# LMH6881-Breakout.net
KiCad netlist of a schematic drawn in EAGLE
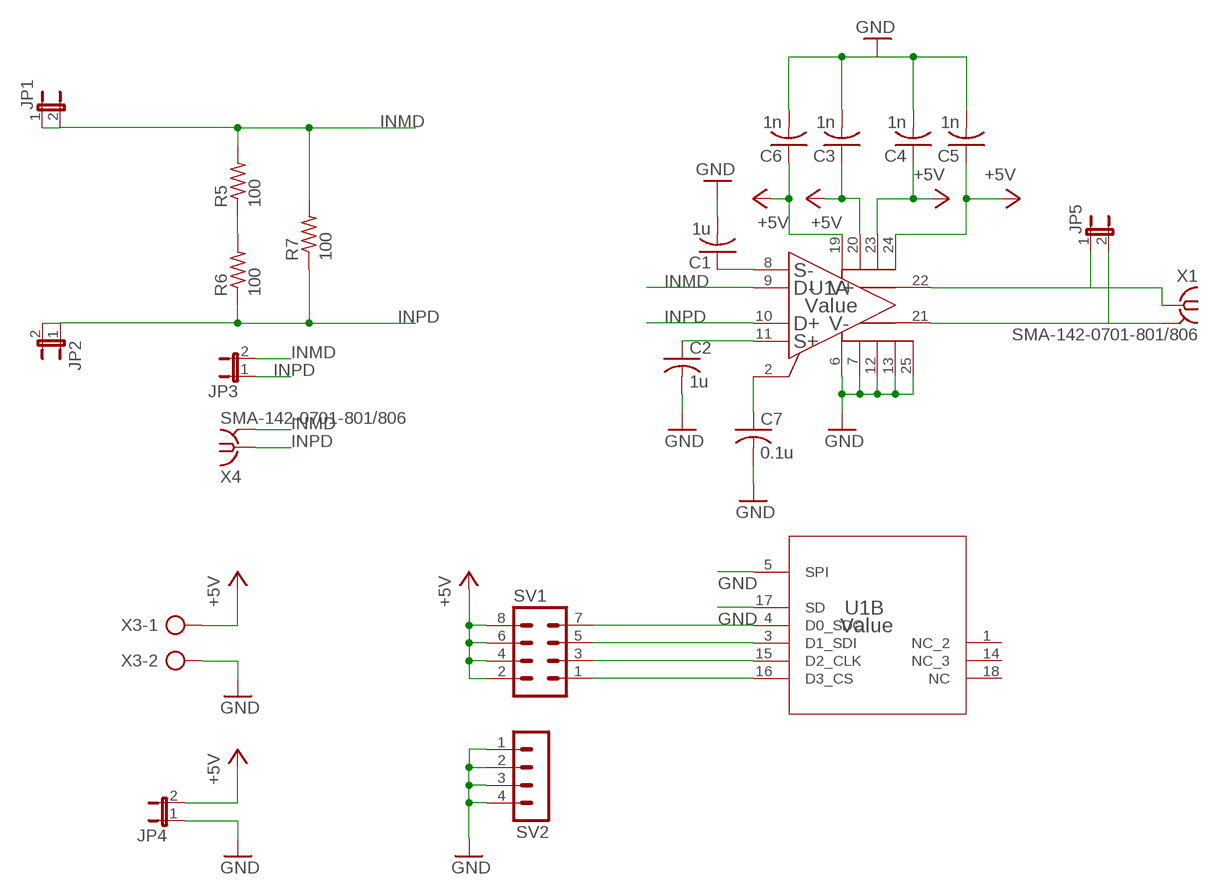
[diagram p0: schematic, sheet 1]

(export (version "E")
  (design (tool "Eeschema 10.0.6"))
  (components
    (comp (ref "C1")
      (value "1u")
      (footprint "eagle-import:C0805")
      (libsource (lib "eagle-import") (part "C-USC0805"))
    )
    (comp (ref "C2")
      (value "1u")
      (footprint "eagle-import:C0805")
      (libsource (lib "eagle-import") (part "C-USC0805"))
    )
    (comp (ref "C3")
      (value "1n")
      (footprint "eagle-import:C0805")
      (libsource (lib "eagle-import") (part "C-USC0805"))
    )
    (comp (ref "C4")
      (value "1n")
      (footprint "eagle-import:C0805")
      (libsource (lib "eagle-import") (part "C-USC0805"))
    )
    (comp (ref "C5")
      (value "1n")
      (footprint "eagle-import:C0805")
      (libsource (lib "eagle-import") (part "C-USC0805"))
    )
    (comp (ref "C6")
      (value "1n")
      (footprint "eagle-import:C0805")
      (libsource (lib "eagle-import") (part "C-USC0805"))
    )
    (comp (ref "C7")
      (value "0.1u")
      (footprint "eagle-import:C0805")
      (libsource (lib "eagle-import") (part "C-USC0805"))
    )
    (comp (ref "JP1")
      (value "JP1E")
      (footprint "eagle-import:JP1")
      (libsource (lib "eagle-import") (part "JP1E"))
    )
    (comp (ref "JP2")
      (value "JP1E")
      (footprint "eagle-import:JP1")
      (libsource (lib "eagle-import") (part "JP1E"))
    )
    (comp (ref "JP3")
      (value "JP1E")
      (footprint "eagle-import:JP1")
      (libsource (lib "eagle-import") (part "JP1E"))
    )
    (comp (ref "JP4")
      (value "JP1E")
      (footprint "eagle-import:JP1")
      (libsource (lib "eagle-import") (part "JP1E"))
    )
    (comp (ref "JP5")
      (value "JP1E")
      (footprint "eagle-import:JP1")
      (libsource (lib "eagle-import") (part "JP1E"))
    )
    (comp (ref "R5")
      (value "100")
      (footprint "eagle-import:R0805")
      (libsource (lib "eagle-import") (part "R-US_R0805"))
    )
    (comp (ref "R6")
      (value "100")
      (footprint "eagle-import:R0805")
      (libsource (lib "eagle-import") (part "R-US_R0805"))
    )
    (comp (ref "R7")
      (value "100")
      (footprint "eagle-import:R0805")
      (libsource (lib "eagle-import") (part "R-US_R0805"))
    )
    (comp (ref "SV1")
      (value "MA04-2")
      (footprint "eagle-import:MA04-2")
      (libsource (lib "eagle-import") (part "MA04-2"))
    )
    (comp (ref "SV2")
      (value "MA04-1")
      (footprint "eagle-import:MA04-1")
      (libsource (lib "eagle-import") (part "MA04-1"))
    )
    (comp (ref "U1")
      (value "Value")
      (footprint "eagle-import:RTW0024A")
      (fields
        (field (name "ALTERNATEPARTNUMBER") "LMH6881SQNOPB")
        (field (name "MANUFACTURER") "Texas Instruments")
        (field (name "PARTNUMBER") "LMH6881SQXNOPB")
      )
      (libsource (lib "eagle-import") (part "LMH6881SQX/NOPB"))
    )
    (comp (ref "X1")
      (value "SMA-142-0701-801/806")
      (footprint "eagle-import:J502-ND-142-0701-801_806")
      (fields (field (name "MF") "JOHNSON COMPONENTS") (field (name "MPN") "142-0701-801"))
      (libsource (lib "eagle-import") (part "SMA-142-0701-801/806"))
    )
    (comp (ref "X3")
      (value "AK500/2")
      (footprint "eagle-import:AK500_2")
      (libsource (lib "eagle-import") (part "AK500/2"))
    )
    (comp (ref "X4")
      (value "SMA-142-0701-801/806")
      (footprint "eagle-import:J502-ND-142-0701-801_806")
      (fields (field (name "MF") "JOHNSON COMPONENTS") (field (name "MPN") "142-0701-801"))
      (libsource (lib "eagle-import") (part "SMA-142-0701-801/806"))
    )
  )
  (nets
    (net (code "1") (name "+5V") (class "Default")
      (node (ref "C3") (pin "1") (pinfunction "1_1") (pintype "passive"))
      (node (ref "C4") (pin "1") (pinfunction "1_1") (pintype "passive"))
      (node (ref "C5") (pin "1") (pinfunction "1_1") (pintype "passive"))
      (node (ref "C6") (pin "1") (pinfunction "1_1") (pintype "passive"))
      (node (ref "JP4") (pin "2") (pinfunction "2_2") (pintype "passive"))
      (node (ref "SV1") (pin "2") (pinfunction "2_2") (pintype "passive"))
      (node (ref "SV1") (pin "4") (pinfunction "4_4") (pintype "passive"))
      (node (ref "SV1") (pin "6") (pinfunction "6_6") (pintype "passive"))
      (node (ref "SV1") (pin "8") (pinfunction "8_8") (pintype "passive"))
      (node (ref "U1") (pin "19") (pinfunction "VCC_2_19") (pintype "power_in"))
      (node (ref "U1") (pin "20") (pinfunction "VCC_3_20") (pintype "power_in"))
      (node (ref "U1") (pin "23") (pinfunction "VCC_4_23") (pintype "power_in"))
      (node (ref "U1") (pin "24") (pinfunction "VCC_24") (pintype "passive"))
      (node (ref "X3") (pin "1") (pinfunction "KL_1") (pintype "passive"))
    )
    (net (code "2") (name "/INMD") (class "Default")
      (node (ref "JP1") (pin "1") (pinfunction "1_1") (pintype "passive"))
      (node (ref "JP1") (pin "2") (pinfunction "2_2") (pintype "passive"))
      (node (ref "JP3") (pin "2") (pinfunction "2_2") (pintype "passive"))
      (node (ref "R5") (pin "2") (pinfunction "2_2") (pintype "passive"))
      (node (ref "R7") (pin "2") (pinfunction "2_2") (pintype "passive"))
      (node (ref "U1") (pin "9") (pinfunction "INMD_9") (pintype "input"))
      (node (ref "X4") (pin "G@1") (pinfunction "2_G@1") (pintype "passive"))
      (node (ref "X4") (pin "G@2") (pinfunction "2_G@2") (pintype "passive"))
      (node (ref "X4") (pin "G@3") (pinfunction "2_G@3") (pintype "passive"))
      (node (ref "X4") (pin "G@4") (pinfunction "2_G@4") (pintype "passive"))
    )
    (net (code "3") (name "/INPD") (class "Default")
      (node (ref "JP2") (pin "1") (pinfunction "1_1") (pintype "passive"))
      (node (ref "JP2") (pin "2") (pinfunction "2_2") (pintype "passive"))
      (node (ref "JP3") (pin "1") (pinfunction "1_1") (pintype "passive"))
      (node (ref "R6") (pin "1") (pinfunction "1_1") (pintype "passive"))
      (node (ref "R7") (pin "1") (pinfunction "1_1") (pintype "passive"))
      (node (ref "U1") (pin "10") (pinfunction "INPD_10") (pintype "input"))
      (node (ref "X4") (pin "1") (pinfunction "1_1") (pintype "passive"))
    )
    (net (code "4") (name "GND") (class "Default")
      (node (ref "C1") (pin "2") (pinfunction "2_2") (pintype "passive"))
      (node (ref "C2") (pin "2") (pinfunction "2_2") (pintype "passive"))
      (node (ref "C3") (pin "2") (pinfunction "2_2") (pintype "passive"))
      (node (ref "C4") (pin "2") (pinfunction "2_2") (pintype "passive"))
      (node (ref "C5") (pin "2") (pinfunction "2_2") (pintype "passive"))
      (node (ref "C6") (pin "2") (pinfunction "2_2") (pintype "passive"))
      (node (ref "C7") (pin "2") (pinfunction "2_2") (pintype "passive"))
      (node (ref "JP4") (pin "1") (pinfunction "1_1") (pintype "passive"))
      (node (ref "SV2") (pin "1") (pinfunction "1_1") (pintype "passive"))
      (node (ref "SV2") (pin "2") (pinfunction "2_2") (pintype "passive"))
      (node (ref "SV2") (pin "3") (pinfunction "3_3") (pintype "passive"))
      (node (ref "SV2") (pin "4") (pinfunction "4_4") (pintype "passive"))
      (node (ref "U1") (pin "12") (pinfunction "GND_4_12") (pintype "power_in"))
      (node (ref "U1") (pin "13") (pinfunction "GND_13") (pintype "power_in"))
      (node (ref "U1") (pin "17") (pinfunction "SD_17") (pintype "input"))
      (node (ref "U1") (pin "25") (pinfunction "PAD_25") (pintype "passive"))
      (node (ref "U1") (pin "5") (pinfunction "SPI_5") (pintype "input"))
      (node (ref "U1") (pin "6") (pinfunction "GND_2_6") (pintype "power_in"))
      (node (ref "U1") (pin "7") (pinfunction "GND_3_7") (pintype "power_in"))
      (node (ref "X3") (pin "2") (pinfunction "KL_2") (pintype "passive"))
    )
    (net (code "5") (name "Net-(R5-Pad1)") (class "Default")
      (node (ref "R5") (pin "1") (pinfunction "1_1") (pintype "passive"))
      (node (ref "R6") (pin "2") (pinfunction "2_2") (pintype "passive"))
    )
    (net (code "6") (name "Net-(U1A-INMS)") (class "Default")
      (node (ref "C1") (pin "1") (pinfunction "1_1") (pintype "passive"))
      (node (ref "U1") (pin "8") (pinfunction "INMS_8") (pintype "input"))
    )
    (net (code "7") (name "Net-(U1A-INPS)") (class "Default")
      (node (ref "C2") (pin "1") (pinfunction "1_1") (pintype "passive"))
      (node (ref "U1") (pin "11") (pinfunction "INPS_11") (pintype "input"))
    )
    (net (code "8") (name "Net-(U1A-OCM)") (class "Default")
      (node (ref "C7") (pin "1") (pinfunction "1_1") (pintype "passive"))
      (node (ref "U1") (pin "2") (pinfunction "OCM_2") (pintype "output"))
    )
    (net (code "9") (name "Net-(U1A-OUTM)") (class "Default")
      (node (ref "JP5") (pin "2") (pinfunction "2_2") (pintype "passive"))
      (node (ref "U1") (pin "21") (pinfunction "OUTM_21") (pintype "output"))
      (node (ref "X1") (pin "G@1") (pinfunction "2_G@1") (pintype "passive"))
      (node (ref "X1") (pin "G@2") (pinfunction "2_G@2") (pintype "passive"))
      (node (ref "X1") (pin "G@3") (pinfunction "2_G@3") (pintype "passive"))
      (node (ref "X1") (pin "G@4") (pinfunction "2_G@4") (pintype "passive"))
    )
    (net (code "10") (name "Net-(U1A-OUTP)") (class "Default")
      (node (ref "JP5") (pin "1") (pinfunction "1_1") (pintype "passive"))
      (node (ref "U1") (pin "22") (pinfunction "OUTP_22") (pintype "output"))
      (node (ref "X1") (pin "1") (pinfunction "1_1") (pintype "passive"))
    )
    (net (code "11") (name "Net-(U1B-D0_SDO)") (class "Default")
      (node (ref "SV1") (pin "7") (pinfunction "7_7") (pintype "passive"))
      (node (ref "U1") (pin "4") (pinfunction "D0_SDO_4") (pintype "bidirectional"))
    )
    (net (code "12") (name "Net-(U1B-D1_SDI)") (class "Default")
      (node (ref "SV1") (pin "5") (pinfunction "5_5") (pintype "passive"))
      (node (ref "U1") (pin "3") (pinfunction "D1_SDI_3") (pintype "input"))
    )
    (net (code "13") (name "Net-(U1B-D2_CLK)") (class "Default")
      (node (ref "SV1") (pin "3") (pinfunction "3_3") (pintype "passive"))
      (node (ref "U1") (pin "15") (pinfunction "D2_CLK_15") (pintype "input"))
    )
    (net (code "14") (name "Net-(U1B-D3_CS)") (class "Default")
      (node (ref "SV1") (pin "1") (pinfunction "1_1") (pintype "passive"))
      (node (ref "U1") (pin "16") (pinfunction "D3_CS_16") (pintype "input"))
    )
    (net (code "15") (name "unconnected-(U1B-NC-Pad18)") (class "Default")
      (node (ref "U1") (pin "18") (pinfunction "NC_18") (pintype "passive"))
    )
    (net (code "16") (name "unconnected-(U1B-NC_2-Pad1)") (class "Default")
      (node (ref "U1") (pin "1") (pinfunction "NC_2_1") (pintype "passive"))
    )
    (net (code "17") (name "unconnected-(U1B-NC_3-Pad14)") (class "Default")
      (node (ref "U1") (pin "14") (pinfunction "NC_3_14") (pintype "passive"))
    )
  )
)
